# Power.net
KiCad netlist of a schematic drawn in Altium Designer
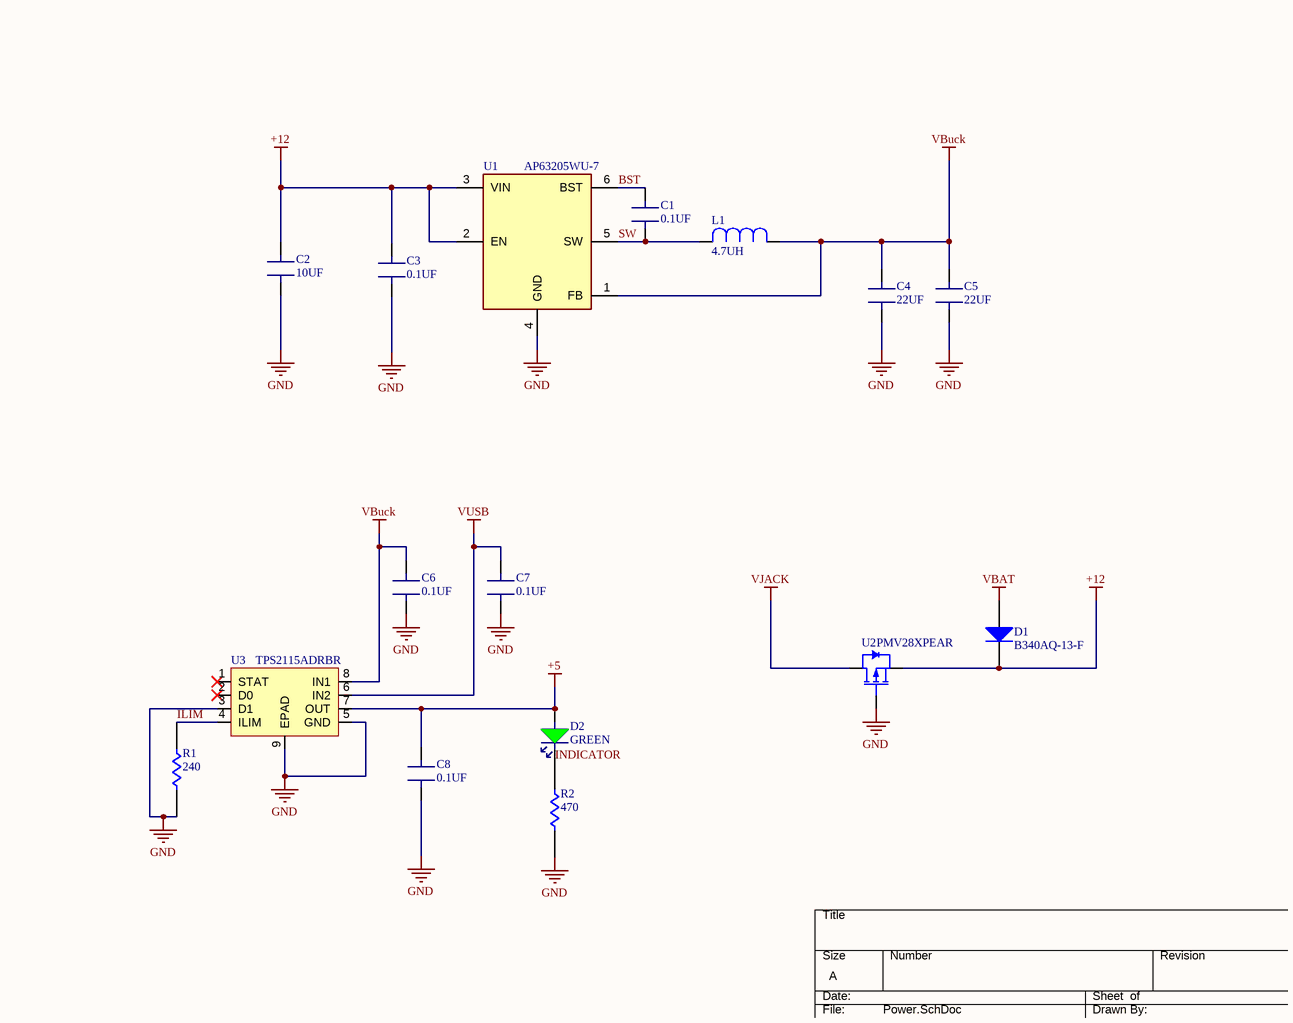
[diagram p0: Power.SchDoc]

(export (version "E")
  (design (tool "Eeschema 10.0.6"))
  (components
    (comp (ref "C1")
      (value "0.1UF")
      (footprint "CAP: 0603")
      (description "CAP CER 0.1UF 50V X7R 0603")
      (libsource (lib "HZSchLib") (part "CL10B104KB8NNNL"))
    )
    (comp (ref "C2")
      (value "10UF")
      (footprint "CAP: 0805")
      (description "CAP CER 10UF 50V X5R 0805")
      (libsource (lib "HZSchLib") (part "GRM21BR61H106KE43L"))
    )
    (comp (ref "C3")
      (value "0.1UF")
      (footprint "CAPC1608X90N")
      (description "CAP CER 0.1UF 50V 10% X7R 0603")
      (libsource (lib "MESchLib") (part "CC0603KRX7R9BB104"))
    )
    (comp (ref "C4")
      (value "22UF")
      (footprint "CAP: 0805")
      (description "CAP CER 22UF 25V X5R 0805")
      (libsource (lib "HZSchLib") (part "CL21A226MAYNNNE"))
    )
    (comp (ref "C5")
      (value "22UF")
      (footprint "CAP: 0805")
      (description "CAP CER 22UF 25V X5R 0805")
      (libsource (lib "HZSchLib") (part "CL21A226MAYNNNE"))
    )
    (comp (ref "C6")
      (value "0.1UF")
      (footprint "CAPC1608X90N")
      (description "CAP CER 0.1UF 50V 10% X7R 0603")
      (libsource (lib "MESchLib") (part "CC0603KRX7R9BB104"))
    )
    (comp (ref "C7")
      (value "0.1UF")
      (footprint "CAPC1608X90N")
      (description "CAP CER 0.1UF 50V 10% X7R 0603")
      (libsource (lib "MESchLib") (part "CC0603KRX7R9BB104"))
    )
    (comp (ref "C8")
      (value "0.1UF")
      (footprint "CAPC1608X90N")
      (description "CAP CER 0.1UF 50V 10% X7R 0603")
      (libsource (lib "MESchLib") (part "CC0603KRX7R9BB104"))
    )
    (comp (ref "D1")
      (value "B340AQ-13-F")
      (footprint "DO-214AC")
      (description "DIODE SCHOTTKY 40V 3A SMA TR 5K")
      (libsource (lib "MESchLib") (part "B340AQ-13-F"))
    )
    (comp (ref "D2")
      (value "GREEN")
      (footprint "LED: 0805G")
      (description "LED GREEN CLEAR 0805 SMD")
      (libsource (lib "MESchLib") (part "732-4983-6-ND"))
    )
    (comp (ref "L1")
      (value "4.7UH")
      (footprint "IND: VLS5045EX-4R7M-H")
      (description "FIXED IND 4.7UH 3.2A 46.8MOHM SM")
      (libsource (lib "HZSchLib") (part "VLS5045EX-4R7M-H"))
    )
    (comp (ref "R1")
      (value "240")
      (footprint "RESC1608X55N")
      (description "RES 240 OHM 5% 1/10W 0603")
      (libsource (lib "MESchLib") (part "RMCF0603JT240RDKR-ND"))
    )
    (comp (ref "R2")
      (value "470")
      (footprint "RESC1608X55N")
      (description "RES 470 OHM 5% 1/10W 0603")
      (libsource (lib "MESchLib") (part "541-4055-6-ND"))
    )
    (comp (ref "U1")
      (value "AP63205WU-7")
      (footprint "TSOT23-6")
      (description "IC REG BUCK 5V 2A TSOT26")
      (libsource (lib "HZSchLib") (part "AP63205WU-7"))
    )
    (comp (ref "U2")
      (value "PMV28XPEAR")
      (footprint "SOT23_3")
      (description "P-Channel 20 V 5A (Ta) 610mW (Ta), 8.3W (Tc) Surface Mount TO-236AB")
      (libsource (lib "MESchLib") (part "PMV28XPEAR"))
    )
    (comp (ref "U3")
      (value "TPS2115ADRBR")
      (footprint "8-SON (3x3)")
      (description "OR Controller Source Selector Switch N-Channel 2:1 8-SON (3x3)")
      (libsource (lib "MESchLib") (part "TPS2115ADRBR"))
    )
  )
  (nets
    (net (code "1") (name "+5") (class "Default")
      (node (ref "C8") (pin "2") (pinfunction "B_2") (pintype "passive"))
      (node (ref "D2") (pin "2") (pinfunction "A_2") (pintype "passive"))
      (node (ref "U3") (pin "7") (pinfunction "OUT_7") (pintype "passive"))
    )
    (net (code "2") (name "+12") (class "Default")
      (node (ref "C2") (pin "2") (pinfunction "B_2") (pintype "passive"))
      (node (ref "C3") (pin "2") (pinfunction "B_2") (pintype "passive"))
      (node (ref "D1") (pin "2") (pinfunction "C_2") (pintype "passive"))
      (node (ref "U1") (pin "2") (pinfunction "EN_2") (pintype "passive"))
      (node (ref "U1") (pin "3") (pinfunction "VIN_3") (pintype "passive"))
      (node (ref "U2") (pin "2") (pinfunction "S_2") (pintype "passive"))
    )
    (net (code "3") (name "/BST") (class "Default")
      (node (ref "C1") (pin "2") (pinfunction "B_2") (pintype "passive"))
      (node (ref "U1") (pin "6") (pinfunction "BST_6") (pintype "passive"))
    )
    (net (code "4") (name "/ILIM") (class "Default")
      (node (ref "R1") (pin "2") (pinfunction "2_2") (pintype "passive"))
      (node (ref "U3") (pin "4") (pinfunction "ILIM_4") (pintype "passive"))
    )
    (net (code "5") (name "/INDICATOR") (class "Default")
      (node (ref "D2") (pin "1") (pinfunction "C_1") (pintype "passive"))
      (node (ref "R2") (pin "2") (pinfunction "2_2") (pintype "passive"))
    )
    (net (code "6") (name "/SW") (class "Default")
      (node (ref "C1") (pin "1") (pinfunction "A_1") (pintype "passive"))
      (node (ref "L1") (pin "1") (pinfunction "1_1") (pintype "passive"))
      (node (ref "U1") (pin "5") (pinfunction "SW_5") (pintype "passive"))
    )
    (net (code "7") (name "GND") (class "Default")
      (node (ref "C2") (pin "1") (pinfunction "A_1") (pintype "passive"))
      (node (ref "C3") (pin "1") (pinfunction "A_1") (pintype "passive"))
      (node (ref "C4") (pin "1") (pinfunction "A_1") (pintype "passive"))
      (node (ref "C5") (pin "1") (pinfunction "A_1") (pintype "passive"))
      (node (ref "C6") (pin "1") (pinfunction "A_1") (pintype "passive"))
      (node (ref "C7") (pin "1") (pinfunction "A_1") (pintype "passive"))
      (node (ref "C8") (pin "1") (pinfunction "A_1") (pintype "passive"))
      (node (ref "R1") (pin "1") (pinfunction "1_1") (pintype "passive"))
      (node (ref "R2") (pin "1") (pinfunction "1_1") (pintype "passive"))
      (node (ref "U1") (pin "4") (pinfunction "GND_4") (pintype "passive"))
      (node (ref "U2") (pin "1") (pinfunction "G_1") (pintype "passive"))
      (node (ref "U3") (pin "3") (pinfunction "D1_3") (pintype "passive"))
      (node (ref "U3") (pin "5") (pinfunction "GND_5") (pintype "passive"))
      (node (ref "U3") (pin "9") (pinfunction "EPAD_9") (pintype "passive"))
    )
    (net (code "8") (name "VBAT") (class "Default")
      (node (ref "D1") (pin "1") (pinfunction "A_1") (pintype "passive"))
    )
    (net (code "9") (name "VBuck") (class "Default")
      (node (ref "C4") (pin "2") (pinfunction "B_2") (pintype "passive"))
      (node (ref "C5") (pin "2") (pinfunction "B_2") (pintype "passive"))
      (node (ref "C6") (pin "2") (pinfunction "B_2") (pintype "passive"))
      (node (ref "L1") (pin "2") (pinfunction "2_2") (pintype "passive"))
      (node (ref "U1") (pin "1") (pinfunction "FB_1") (pintype "passive"))
      (node (ref "U3") (pin "8") (pinfunction "IN1_8") (pintype "passive"))
    )
    (net (code "10") (name "VJACK") (class "Default")
      (node (ref "U2") (pin "3") (pinfunction "D_3") (pintype "passive"))
    )
    (net (code "11") (name "VUSB") (class "Default")
      (node (ref "C7") (pin "2") (pinfunction "B_2") (pintype "passive"))
      (node (ref "U3") (pin "6") (pinfunction "IN2_6") (pintype "passive"))
    )
    (net (code "12") (name "unconnected-(U3-D0-Pad2)") (class "Default")
      (node (ref "U3") (pin "2") (pinfunction "D0_2") (pintype "passive+no_connect"))
    )
    (net (code "13") (name "unconnected-(U3-STAT-Pad1)") (class "Default")
      (node (ref "U3") (pin "1") (pinfunction "STAT_1") (pintype "passive+no_connect"))
    )
  )
)
